# testx2.net
KiCad netlist of a schematic drawn in EAGLE
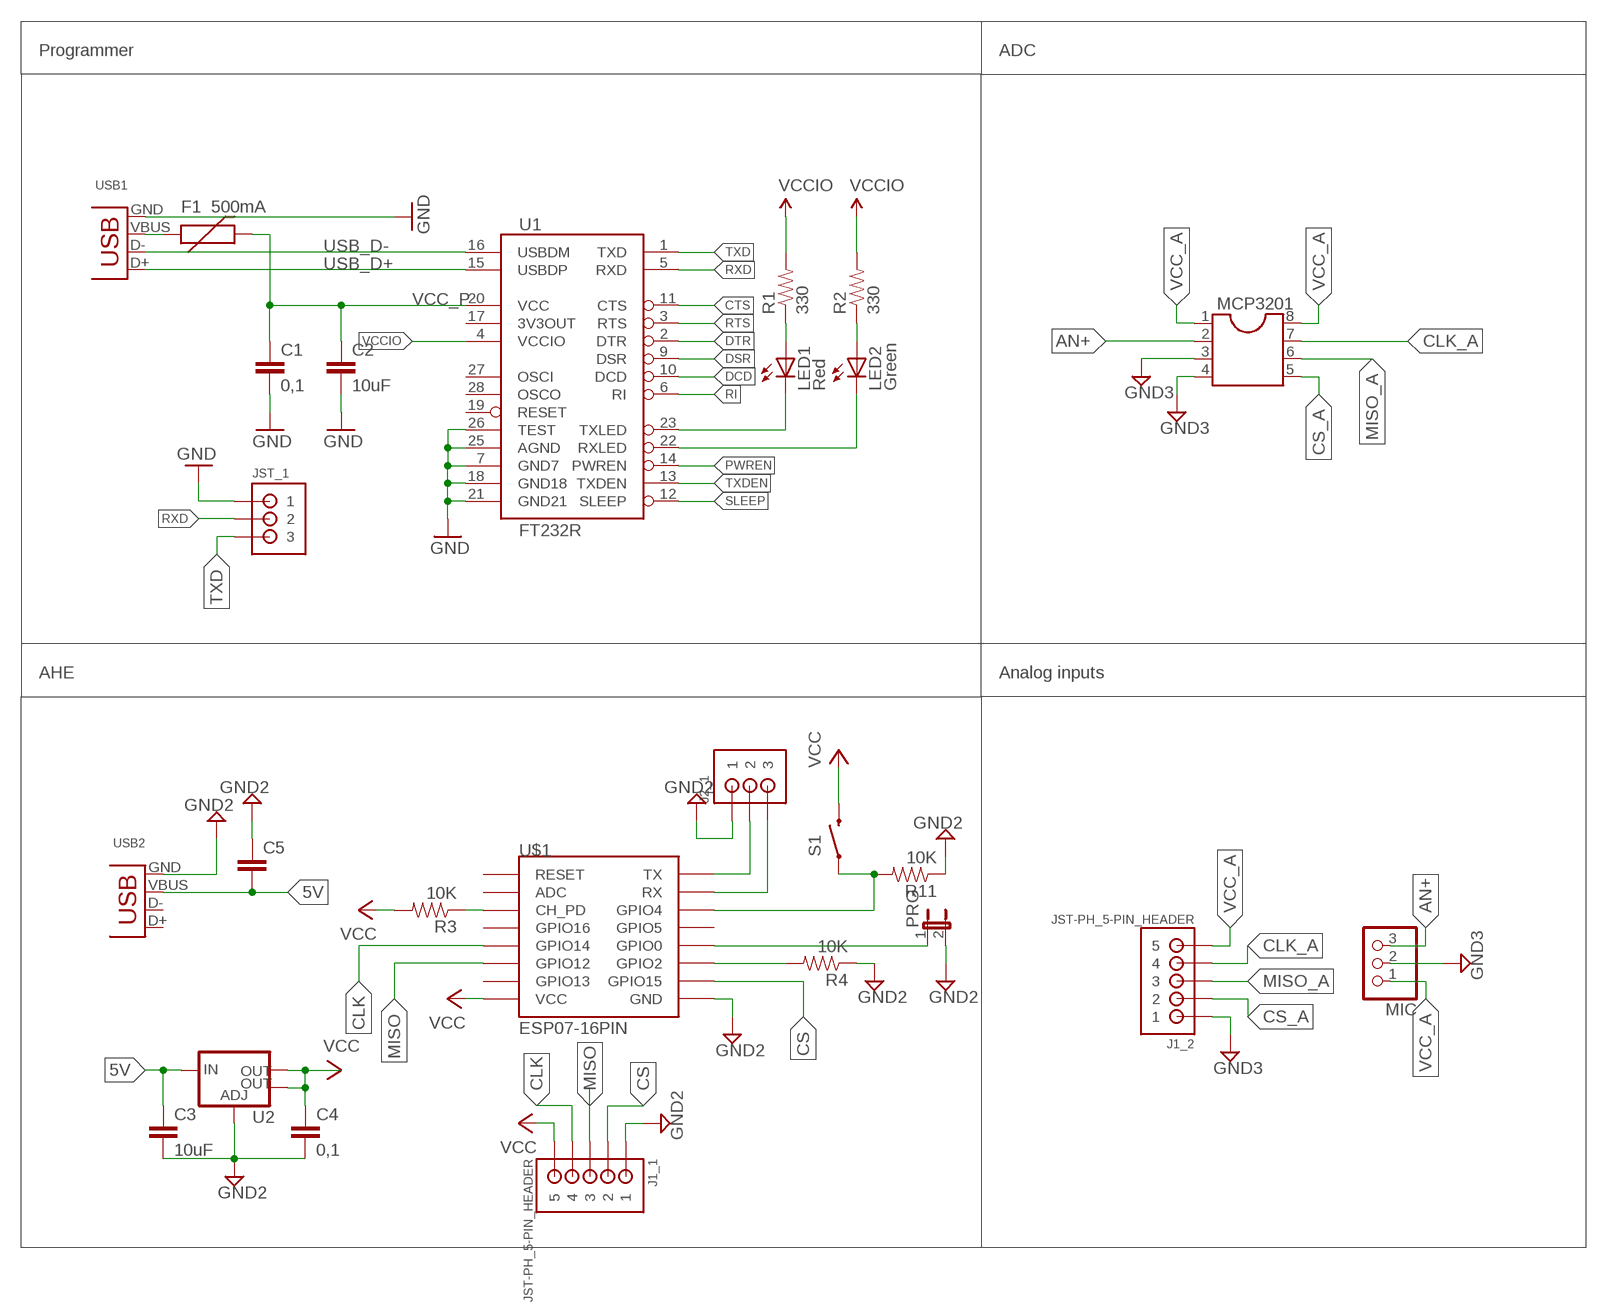
[diagram p0: schematic, sheet 1]
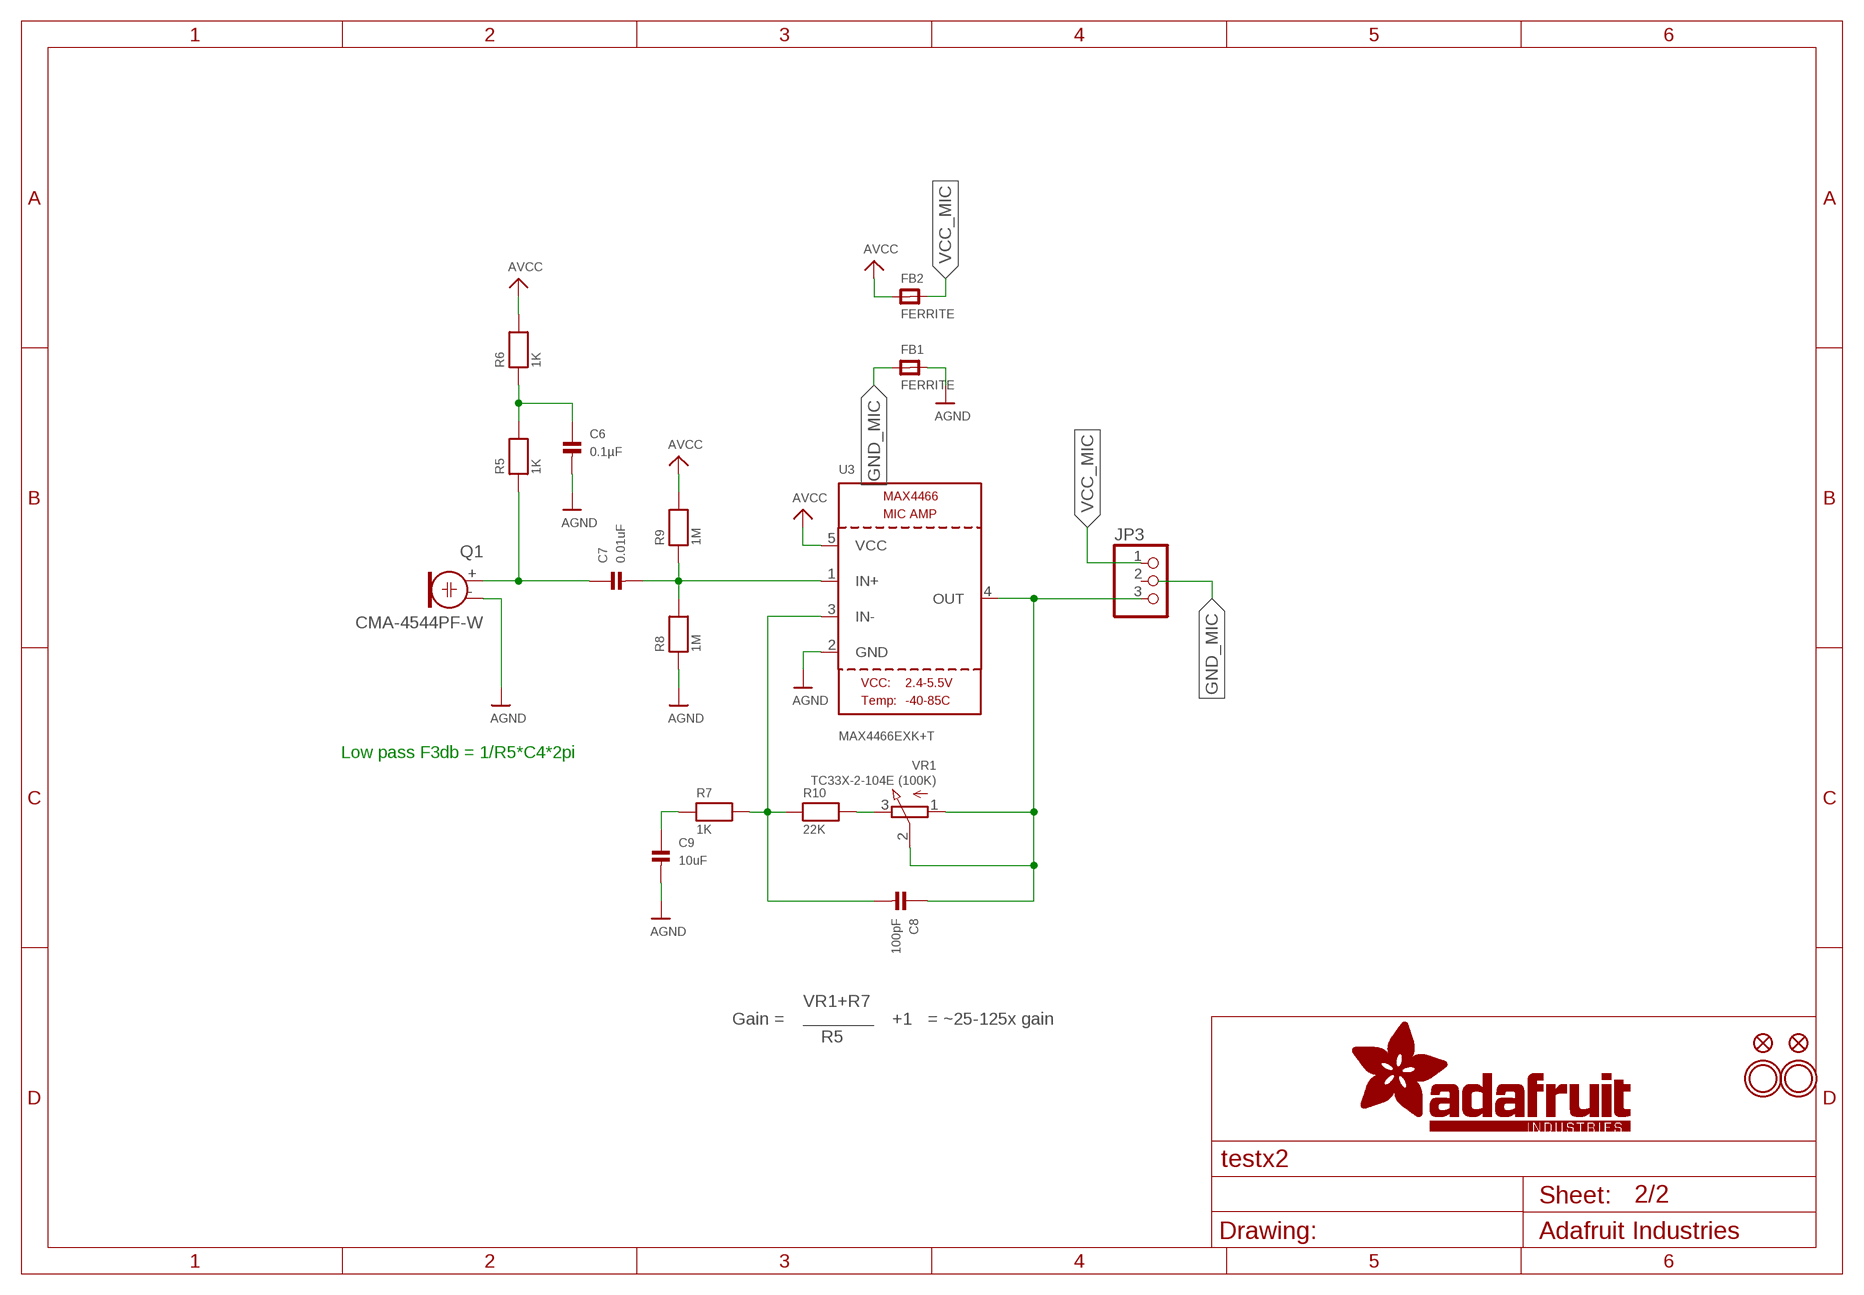
[diagram p1: schematic, sheet 2]

(export (version "E")
  (design (tool "Eeschema 10.0.6"))
  (components
    (comp (ref "C1")
      (value "0,1")
      (footprint "eagle-import:0805-CAP")
      (libsource (lib "eagle-import") (part "10UF10V10%(0805)"))
    )
    (comp (ref "C2")
      (value "10uF")
      (footprint "eagle-import:0805-CAP")
      (libsource (lib "eagle-import") (part "10UF10V10%(0805)"))
    )
    (comp (ref "C3")
      (value "10uF")
      (footprint "eagle-import:0805-CAP")
      (libsource (lib "eagle-import") (part "10UF10V10%(0805)"))
    )
    (comp (ref "C4")
      (value "0,1")
      (footprint "eagle-import:0805-CAP")
      (libsource (lib "eagle-import") (part "10UF10V10%(0805)"))
    )
    (comp (ref "C5")
      (value "CAP_")
      (footprint "eagle-import:AXIAL-5MM")
      (libsource (lib "eagle-import") (part "CAP_"))
    )
    (comp (ref "F1")
      (value "500mA")
      (footprint "eagle-import:PTC-1206")
      (libsource (lib "eagle-import") (part "PTCSMD"))
    )
    (comp (ref "J1_1")
      (value "JST-PH_5-PIN_HEADER")
      (footprint "eagle-import:JST_B5B-PH_HEADER")
      (libsource (lib "eagle-import") (part "JST-PH_5-PIN_HEADER"))
    )
    (comp (ref "J1_2")
      (value "JST-PH_5-PIN_HEADER")
      (footprint "eagle-import:JST_B5B-PH_HEADER")
      (libsource (lib "eagle-import") (part "JST-PH_5-PIN_HEADER"))
    )
    (comp (ref "J2_1")
      (value "JST-PH_3-PIN_HEADER")
      (footprint "eagle-import:JST_B3B-PH_HEADER")
      (libsource (lib "eagle-import") (part "JST-PH_3-PIN_HEADER"))
    )
    (comp (ref "JST_1")
      (value "JST-PH_3-PIN_HEADER")
      (footprint "eagle-import:JST_B3B-PH_HEADER")
      (libsource (lib "eagle-import") (part "JST-PH_3-PIN_HEADER"))
    )
    (comp (ref "LED1")
      (value "Red")
      (footprint "eagle-import:SML0805")
      (libsource (lib "eagle-import") (part "LEDSML0805"))
    )
    (comp (ref "LED2")
      (value "Green")
      (footprint "eagle-import:SML0805")
      (libsource (lib "eagle-import") (part "LEDSML0805"))
    )
    (comp (ref "MCP3201")
      (value "DIL8")
      (footprint "eagle-import:DIL08")
      (libsource (lib "eagle-import") (part "DIL8"))
    )
    (comp (ref "MIC")
      (value "PINHD-1X03_2.54-S")
      (footprint "eagle-import:1X03-S")
      (libsource (lib "eagle-import") (part "PINHD-1X03_2.54-S"))
    )
    (comp (ref "PRG")
      (value "JP1E")
      (footprint "eagle-import:JP1")
      (libsource (lib "eagle-import") (part "JP1E"))
    )
    (comp (ref "R1")
      (value "330")
      (footprint "eagle-import:0805")
      (libsource (lib "eagle-import") (part "0.22OHM-1/4W-1%(0805)"))
    )
    (comp (ref "R2")
      (value "330")
      (footprint "eagle-import:0805")
      (libsource (lib "eagle-import") (part "0.22OHM-1/4W-1%(0805)"))
    )
    (comp (ref "R3")
      (value "10K")
      (footprint "eagle-import:0805")
      (libsource (lib "eagle-import") (part "0.22OHM-1/4W-1%(0805)"))
    )
    (comp (ref "R4")
      (value "10K")
      (footprint "eagle-import:0805")
      (libsource (lib "eagle-import") (part "0.22OHM-1/4W-1%(0805)"))
    )
    (comp (ref "R11")
      (value "10K")
      (footprint "eagle-import:0805")
      (libsource (lib "eagle-import") (part "0.22OHM-1/4W-1%(0805)"))
    )
    (comp (ref "S1")
      (value "SWITCH-MOMENTARY-2PTH")
      (footprint "eagle-import:TACTILE-PTH")
      (libsource (lib "eagle-import") (part "SWITCH-MOMENTARY-2PTH"))
    )
    (comp (ref "U$1")
      (value "ESP07-16PIN")
      (footprint "eagle-import:ESP07-16PIN")
      (libsource (lib "eagle-import") (part "ESP07-16PIN"))
    )
    (comp (ref "U1")
      (value "FT232R")
      (footprint "eagle-import:SSOP28DB")
      (libsource (lib "eagle-import") (part "FT232RLSSOP"))
    )
    (comp (ref "U2")
      (value "V_REG_LM1117SOT223")
      (footprint "eagle-import:SOT223")
      (libsource (lib "eagle-import") (part "V_REG_LM1117SOT223"))
    )
    (comp (ref "USB1")
      (value "USB-MB-S")
      (footprint "eagle-import:USB-MB-S")
      (libsource (lib "eagle-import") (part "USB-MB-S"))
    )
    (comp (ref "USB2")
      (value "USB-MB-S")
      (footprint "eagle-import:USB-MB-S")
      (libsource (lib "eagle-import") (part "USB-MB-S"))
    )
    (comp (ref "C6")
      (value "0.1µF")
      (footprint "eagle-import:0805")
      (libsource (lib "eagle-import") (part "CAP_CERAMIC0805"))
    )
    (comp (ref "C7")
      (value "0.01uF")
      (footprint "eagle-import:0805")
      (libsource (lib "eagle-import") (part "CAP_CERAMIC0805"))
    )
    (comp (ref "C8")
      (value "100pF")
      (footprint "eagle-import:0805")
      (libsource (lib "eagle-import") (part "CAP_CERAMIC0805"))
    )
    (comp (ref "C9")
      (value "10uF")
      (footprint "eagle-import:0805")
      (libsource (lib "eagle-import") (part "CAP_CERAMIC0805"))
    )
    (comp (ref "FB1")
      (value "FERRITE")
      (footprint "eagle-import:0805")
      (libsource (lib "eagle-import") (part "FERRITE0805"))
    )
    (comp (ref "FB2")
      (value "FERRITE")
      (footprint "eagle-import:0805")
      (libsource (lib "eagle-import") (part "FERRITE0805"))
    )
    (comp (ref "FID1")
      (value "FIDUCIAL\"\"")
      (footprint "eagle-import:FIDUCIAL_1MM")
      (libsource (lib "eagle-import") (part "FIDUCIAL{dblquote}{dblquote}"))
    )
    (comp (ref "FID2")
      (value "FIDUCIAL\"\"")
      (footprint "eagle-import:FIDUCIAL_1MM")
      (libsource (lib "eagle-import") (part "FIDUCIAL{dblquote}{dblquote}"))
    )
    (comp (ref "JP3")
      (value "HEADER-1X376MIL")
      (footprint "eagle-import:1X03_ROUND_76")
      (libsource (lib "eagle-import") (part "HEADER-1X376MIL"))
    )
    (comp (ref "Q1")
      (value "CMA-4544PF-W")
      (footprint "eagle-import:ELECTRET_9.7")
      (libsource (lib "eagle-import") (part "ELECTRET"))
    )
    (comp (ref "R5")
      (value "1K")
      (footprint "eagle-import:0805")
      (libsource (lib "eagle-import") (part "RESISTOR0805"))
    )
    (comp (ref "R6")
      (value "1K")
      (footprint "eagle-import:0805")
      (libsource (lib "eagle-import") (part "RESISTOR0805"))
    )
    (comp (ref "R7")
      (value "1K")
      (footprint "eagle-import:0805")
      (libsource (lib "eagle-import") (part "RESISTOR0805"))
    )
    (comp (ref "R8")
      (value "1M")
      (footprint "eagle-import:0805")
      (libsource (lib "eagle-import") (part "RESISTOR0805"))
    )
    (comp (ref "R9")
      (value "1M")
      (footprint "eagle-import:0805")
      (libsource (lib "eagle-import") (part "RESISTOR0805"))
    )
    (comp (ref "R10")
      (value "22K")
      (footprint "eagle-import:0805")
      (libsource (lib "eagle-import") (part "RESISTOR0805"))
    )
    (comp (ref "U$16")
      (value "MOUNTINGHOLE2.5")
      (footprint "eagle-import:MOUNTINGHOLE_2.5_PLATED")
      (libsource (lib "eagle-import") (part "MOUNTINGHOLE2.5"))
    )
    (comp (ref "U$17")
      (value "MOUNTINGHOLE2.5")
      (footprint "eagle-import:MOUNTINGHOLE_2.5_PLATED")
      (libsource (lib "eagle-import") (part "MOUNTINGHOLE2.5"))
    )
    (comp (ref "U3")
      (value "MAX4466EXK+T")
      (footprint "eagle-import:SC70-5")
      (libsource (lib "eagle-import") (part "MAX4466{dblquote}{dblquote}"))
    )
    (comp (ref "VR1")
      (value "TC33X-2-104E (100K)")
      (footprint "eagle-import:TRIMPOT_BOURNS_TC33X-2")
      (libsource (lib "eagle-import") (part "TRIMPOTTC33X-2"))
    )
  )
  (nets
    (net (code "1") (name "5V") (class "Default")
      (node (ref "C3") (pin "1") (pinfunction "1_1") (pintype "passive"))
      (node (ref "C5") (pin "P$2") (pinfunction "2_P$2") (pintype "passive"))
      (node (ref "U2") (pin "3") (pinfunction "IN_3") (pintype "input"))
      (node (ref "USB2") (pin "VBUS") (pinfunction "VBUS_VBUS") (pintype "bidirectional"))
    )
    (net (code "2") (name "AGND") (class "Default")
      (node (ref "C6") (pin "2") (pinfunction "P$2_2") (pintype "passive"))
      (node (ref "C9") (pin "2") (pinfunction "P$2_2") (pintype "passive"))
      (node (ref "FB1") (pin "2") (pinfunction "P$2_2") (pintype "passive"))
      (node (ref "Q1") (pin "-") (pinfunction "1_-") (pintype "passive"))
      (node (ref "R8") (pin "1") (pinfunction "1_1") (pintype "passive"))
      (node (ref "U3") (pin "2") (pinfunction "GND_2") (pintype "bidirectional"))
    )
    (net (code "3") (name "AN+") (class "Default")
      (node (ref "MCP3201") (pin "2") (pinfunction "2_2") (pintype "passive"))
      (node (ref "MIC") (pin "3") (pinfunction "3_3") (pintype "passive"))
    )
    (net (code "4") (name "AVCC") (class "Default")
      (node (ref "FB2") (pin "1") (pinfunction "P$1_1") (pintype "passive"))
      (node (ref "R6") (pin "2") (pinfunction "2_2") (pintype "passive"))
      (node (ref "R9") (pin "2") (pinfunction "2_2") (pintype "passive"))
      (node (ref "U3") (pin "5") (pinfunction "VCC_5") (pintype "bidirectional"))
    )
    (net (code "5") (name "CLK") (class "Default")
      (node (ref "J1_1") (pin "P4") (pinfunction "4_P4") (pintype "bidirectional"))
      (node (ref "U$1") (pin "GPIO14") (pinfunction "GPIO14_GPIO14") (pintype "bidirectional"))
    )
    (net (code "6") (name "CLK_A") (class "Default")
      (node (ref "J1_2") (pin "P4") (pinfunction "4_P4") (pintype "bidirectional"))
      (node (ref "MCP3201") (pin "7") (pinfunction "7_7") (pintype "passive"))
    )
    (net (code "7") (name "CS") (class "Default")
      (node (ref "J1_1") (pin "P2") (pinfunction "2_P2") (pintype "bidirectional"))
      (node (ref "U$1") (pin "GPIO15") (pinfunction "GPIO15_GPIO15") (pintype "bidirectional"))
    )
    (net (code "8") (name "CS_A") (class "Default")
      (node (ref "J1_2") (pin "P2") (pinfunction "2_P2") (pintype "bidirectional"))
      (node (ref "MCP3201") (pin "5") (pinfunction "5_5") (pintype "passive"))
    )
    (net (code "9") (name "CTS") (class "Default")
      (node (ref "U1") (pin "11") (pinfunction "CTS_11") (pintype "input"))
    )
    (net (code "10") (name "DCD") (class "Default")
      (node (ref "U1") (pin "10") (pinfunction "DCD_10") (pintype "input"))
    )
    (net (code "11") (name "DSR") (class "Default")
      (node (ref "U1") (pin "9") (pinfunction "DSR_9") (pintype "input"))
    )
    (net (code "12") (name "DTR") (class "Default")
      (node (ref "U1") (pin "2") (pinfunction "DTR_2") (pintype "output"))
    )
    (net (code "13") (name "GND") (class "Default")
      (node (ref "C1") (pin "2") (pinfunction "2_2") (pintype "passive"))
      (node (ref "C2") (pin "2") (pinfunction "2_2") (pintype "passive"))
      (node (ref "JST_1") (pin "P1") (pinfunction "1_P1") (pintype "bidirectional"))
      (node (ref "U1") (pin "18") (pinfunction "GND18_18") (pintype "power_in"))
      (node (ref "U1") (pin "21") (pinfunction "GND21_21") (pintype "power_in"))
      (node (ref "U1") (pin "25") (pinfunction "AGND_25") (pintype "power_in"))
      (node (ref "U1") (pin "26") (pinfunction "TEST_26") (pintype "input"))
      (node (ref "U1") (pin "7") (pinfunction "GND7_7") (pintype "power_in"))
      (node (ref "USB1") (pin "GND") (pinfunction "GND_GND") (pintype "bidirectional"))
    )
    (net (code "14") (name "GND2") (class "Default")
      (node (ref "C3") (pin "2") (pinfunction "2_2") (pintype "passive"))
      (node (ref "C4") (pin "2") (pinfunction "2_2") (pintype "passive"))
      (node (ref "C5") (pin "P$1") (pinfunction "1_P$1") (pintype "passive"))
      (node (ref "J1_1") (pin "P1") (pinfunction "1_P1") (pintype "bidirectional"))
      (node (ref "J2_1") (pin "P1") (pinfunction "1_P1") (pintype "bidirectional"))
      (node (ref "PRG") (pin "2") (pinfunction "2_2") (pintype "passive"))
      (node (ref "R11") (pin "1") (pinfunction "1_1") (pintype "passive"))
      (node (ref "R4") (pin "1") (pinfunction "1_1") (pintype "passive"))
      (node (ref "U$1") (pin "GND") (pinfunction "GND_GND") (pintype "bidirectional"))
      (node (ref "U2") (pin "1") (pinfunction "ADJ_1") (pintype "input"))
      (node (ref "USB2") (pin "GND") (pinfunction "GND_GND") (pintype "bidirectional"))
    )
    (net (code "15") (name "GND3") (class "Default")
      (node (ref "J1_2") (pin "P1") (pinfunction "1_P1") (pintype "bidirectional"))
      (node (ref "MCP3201") (pin "3") (pinfunction "3_3") (pintype "passive"))
      (node (ref "MCP3201") (pin "4") (pinfunction "4_4") (pintype "passive"))
      (node (ref "MIC") (pin "2") (pinfunction "2_2") (pintype "passive"))
    )
    (net (code "16") (name "GND_MIC") (class "Default")
      (node (ref "FB1") (pin "1") (pinfunction "P$1_1") (pintype "passive"))
    )
    (net (code "17") (name "MISO") (class "Default")
      (node (ref "J1_1") (pin "P3") (pinfunction "3_P3") (pintype "bidirectional"))
      (node (ref "U$1") (pin "GPIO12") (pinfunction "GPIO12_GPIO12") (pintype "bidirectional"))
    )
    (net (code "18") (name "MISO_A") (class "Default")
      (node (ref "J1_2") (pin "P3") (pinfunction "3_P3") (pintype "bidirectional"))
      (node (ref "MCP3201") (pin "6") (pinfunction "6_6") (pintype "passive"))
    )
    (net (code "19") (name "Net-(C6-P$1)") (class "Default")
      (node (ref "C6") (pin "1") (pinfunction "P$1_1") (pintype "passive"))
      (node (ref "R5") (pin "2") (pinfunction "2_2") (pintype "passive"))
      (node (ref "R6") (pin "1") (pinfunction "1_1") (pintype "passive"))
    )
    (net (code "20") (name "Net-(C7-P$1)") (class "Default")
      (node (ref "C7") (pin "1") (pinfunction "P$1_1") (pintype "passive"))
      (node (ref "Q1") (pin "+") (pinfunction "2_+") (pintype "passive"))
      (node (ref "R5") (pin "1") (pinfunction "1_1") (pintype "passive"))
    )
    (net (code "21") (name "Net-(C7-P$2)") (class "Default")
      (node (ref "C7") (pin "2") (pinfunction "P$2_2") (pintype "passive"))
      (node (ref "R8") (pin "2") (pinfunction "2_2") (pintype "passive"))
      (node (ref "R9") (pin "1") (pinfunction "1_1") (pintype "passive"))
      (node (ref "U3") (pin "1") (pinfunction "IN+_1") (pintype "bidirectional"))
    )
    (net (code "22") (name "Net-(C8-P$1)") (class "Default")
      (node (ref "C8") (pin "1") (pinfunction "P$1_1") (pintype "passive"))
      (node (ref "JP3") (pin "3") (pinfunction "3_3") (pintype "passive"))
      (node (ref "U3") (pin "4") (pinfunction "OUT_4") (pintype "bidirectional"))
      (node (ref "VR1") (pin "1") (pinfunction "A_1") (pintype "passive"))
      (node (ref "VR1") (pin "2") (pinfunction "S_2") (pintype "passive"))
    )
    (net (code "23") (name "Net-(C8-P$2)") (class "Default")
      (node (ref "C8") (pin "2") (pinfunction "P$2_2") (pintype "passive"))
      (node (ref "R10") (pin "1") (pinfunction "1_1") (pintype "passive"))
      (node (ref "R7") (pin "2") (pinfunction "2_2") (pintype "passive"))
      (node (ref "U3") (pin "3") (pinfunction "IN-_3") (pintype "bidirectional"))
    )
    (net (code "24") (name "Net-(C9-P$1)") (class "Default")
      (node (ref "C9") (pin "1") (pinfunction "P$1_1") (pintype "passive"))
      (node (ref "R7") (pin "1") (pinfunction "1_1") (pintype "passive"))
    )
    (net (code "25") (name "Net-(F1-Pad1)") (class "Default")
      (node (ref "F1") (pin "1") (pinfunction "1_1") (pintype "bidirectional"))
      (node (ref "USB1") (pin "VBUS") (pinfunction "VBUS_VBUS") (pintype "bidirectional"))
    )
    (net (code "26") (name "Net-(J2_1-2)") (class "Default")
      (node (ref "J2_1") (pin "P2") (pinfunction "2_P2") (pintype "bidirectional"))
      (node (ref "U$1") (pin "TX") (pinfunction "TX_TX") (pintype "bidirectional"))
    )
    (net (code "27") (name "Net-(J2_1-3)") (class "Default")
      (node (ref "J2_1") (pin "P3") (pinfunction "3_P3") (pintype "bidirectional"))
      (node (ref "U$1") (pin "RX") (pinfunction "RX_RX") (pintype "bidirectional"))
    )
    (net (code "28") (name "Net-(LED1-PadA)") (class "Default")
      (node (ref "LED1") (pin "A") (pinfunction "A_A") (pintype "passive"))
      (node (ref "R1") (pin "1") (pinfunction "1_1") (pintype "passive"))
    )
    (net (code "29") (name "Net-(LED2-PadA)") (class "Default")
      (node (ref "LED2") (pin "A") (pinfunction "A_A") (pintype "passive"))
      (node (ref "R2") (pin "1") (pinfunction "1_1") (pintype "passive"))
    )
    (net (code "30") (name "Net-(PRG-Pad1)") (class "Default")
      (node (ref "PRG") (pin "1") (pinfunction "1_1") (pintype "passive"))
      (node (ref "U$1") (pin "GPIO0") (pinfunction "GPIO0_GPIO0") (pintype "bidirectional"))
    )
    (net (code "31") (name "Net-(R3-Pad1)") (class "Default")
      (node (ref "R3") (pin "1") (pinfunction "1_1") (pintype "passive"))
      (node (ref "U$1") (pin "CH_PD") (pinfunction "CH_PD_CH_PD") (pintype "bidirectional"))
    )
    (net (code "32") (name "Net-(R4-Pad2)") (class "Default")
      (node (ref "R4") (pin "2") (pinfunction "2_2") (pintype "passive"))
      (node (ref "U$1") (pin "GPIO2") (pinfunction "GPIO2_GPIO2") (pintype "bidirectional"))
    )
    (net (code "33") (name "Net-(R11-Pad2)") (class "Default")
      (node (ref "R11") (pin "2") (pinfunction "2_2") (pintype "passive"))
      (node (ref "S1") (pin "1") (pinfunction "1_1") (pintype "passive"))
      (node (ref "U$1") (pin "GPIO4") (pinfunction "GPIO4_GPIO4") (pintype "bidirectional"))
    )
    (net (code "34") (name "Net-(U1-RXLED)") (class "Default")
      (node (ref "LED2") (pin "C") (pinfunction "C_C") (pintype "passive"))
      (node (ref "U1") (pin "22") (pinfunction "RXLED_22") (pintype "input"))
    )
    (net (code "35") (name "Net-(U1-TXLED)") (class "Default")
      (node (ref "LED1") (pin "C") (pinfunction "C_C") (pintype "passive"))
      (node (ref "U1") (pin "23") (pinfunction "TXLED_23") (pintype "input"))
    )
    (net (code "36") (name "Net-(VR1-E)") (class "Default")
      (node (ref "R10") (pin "2") (pinfunction "2_2") (pintype "passive"))
      (node (ref "VR1") (pin "3") (pinfunction "E_3") (pintype "passive"))
    )
    (net (code "37") (name "PWREN") (class "Default")
      (node (ref "U1") (pin "14") (pinfunction "PWREN_14") (pintype "input"))
    )
    (net (code "38") (name "RI") (class "Default")
      (node (ref "U1") (pin "6") (pinfunction "RI_6") (pintype "input"))
    )
    (net (code "39") (name "RTS") (class "Default")
      (node (ref "U1") (pin "3") (pinfunction "RTS_3") (pintype "output"))
    )
    (net (code "40") (name "RXD") (class "Default")
      (node (ref "JST_1") (pin "P2") (pinfunction "2_P2") (pintype "bidirectional"))
      (node (ref "U1") (pin "5") (pinfunction "RXD_5") (pintype "input"))
    )
    (net (code "41") (name "SLEEP") (class "Default")
      (node (ref "U1") (pin "12") (pinfunction "SLEEP_12") (pintype "input"))
    )
    (net (code "42") (name "TXD") (class "Default")
      (node (ref "JST_1") (pin "P3") (pinfunction "3_P3") (pintype "bidirectional"))
      (node (ref "U1") (pin "1") (pinfunction "TXD_1") (pintype "output"))
    )
    (net (code "43") (name "TXDEN") (class "Default")
      (node (ref "U1") (pin "13") (pinfunction "TXDEN_13") (pintype "input"))
    )
    (net (code "44") (name "USB_D+") (class "Default")
      (node (ref "U1") (pin "15") (pinfunction "USBDP_15") (pintype "bidirectional"))
      (node (ref "USB1") (pin "D+") (pinfunction "D+_D+") (pintype "bidirectional"))
    )
    (net (code "45") (name "USB_D-") (class "Default")
      (node (ref "U1") (pin "16") (pinfunction "USBDM_16") (pintype "bidirectional"))
      (node (ref "USB1") (pin "D-") (pinfunction "D-_D-") (pintype "bidirectional"))
    )
    (net (code "46") (name "VCC") (class "Default")
      (node (ref "C4") (pin "1") (pinfunction "1_1") (pintype "passive"))
      (node (ref "J1_1") (pin "P5") (pinfunction "5_P5") (pintype "bidirectional"))
      (node (ref "R3") (pin "2") (pinfunction "2_2") (pintype "passive"))
      (node (ref "S1") (pin "3") (pinfunction "2_3") (pintype "passive"))
      (node (ref "U$1") (pin "VCC") (pinfunction "VCC_VCC") (pintype "bidirectional"))
      (node (ref "U2") (pin "2") (pinfunction "OUT_2") (pintype "output"))
      (node (ref "U2") (pin "4") (pinfunction "OUT_4") (pintype "output"))
    )
    (net (code "47") (name "VCCIO") (class "Default")
      (node (ref "R1") (pin "2") (pinfunction "2_2") (pintype "passive"))
      (node (ref "R2") (pin "2") (pinfunction "2_2") (pintype "passive"))
      (node (ref "U1") (pin "4") (pinfunction "VCCIO_4") (pintype "power_in"))
    )
    (net (code "48") (name "VCC_A") (class "Default")
      (node (ref "J1_2") (pin "P5") (pinfunction "5_P5") (pintype "bidirectional"))
      (node (ref "MCP3201") (pin "1") (pinfunction "1_1") (pintype "passive"))
      (node (ref "MCP3201") (pin "8") (pinfunction "8_8") (pintype "passive"))
      (node (ref "MIC") (pin "1") (pinfunction "1_1") (pintype "passive"))
    )
    (net (code "49") (name "VCC_MIC") (class "Default")
      (node (ref "FB2") (pin "2") (pinfunction "P$2_2") (pintype "passive"))
      (node (ref "JP3") (pin "1") (pinfunction "1_1") (pintype "passive"))
    )
    (net (code "50") (name "VCC_P") (class "Default")
      (node (ref "C1") (pin "1") (pinfunction "1_1") (pintype "passive"))
      (node (ref "C2") (pin "1") (pinfunction "1_1") (pintype "passive"))
      (node (ref "F1") (pin "2") (pinfunction "2_2") (pintype "bidirectional"))
      (node (ref "U1") (pin "20") (pinfunction "VCC_20") (pintype "power_in"))
    )
    (net (code "51") (name "unconnected-(JP3-Pad2)") (class "Default")
      (node (ref "JP3") (pin "2") (pinfunction "2_2") (pintype "passive"))
    )
    (net (code "52") (name "unconnected-(U$1-PadADC)") (class "Default")
      (node (ref "U$1") (pin "ADC") (pinfunction "ADC_ADC") (pintype "bidirectional"))
    )
    (net (code "53") (name "unconnected-(U$1-PadGPIO5)") (class "Default")
      (node (ref "U$1") (pin "GPIO5") (pinfunction "GPIO5_GPIO5") (pintype "bidirectional"))
    )
    (net (code "54") (name "unconnected-(U$1-PadGPIO13)") (class "Default")
      (node (ref "U$1") (pin "GPIO13") (pinfunction "GPIO13_GPIO13") (pintype "bidirectional"))
    )
    (net (code "55") (name "unconnected-(U$1-PadGPIO16)") (class "Default")
      (node (ref "U$1") (pin "GPIO16") (pinfunction "GPIO16_GPIO16") (pintype "bidirectional"))
    )
    (net (code "56") (name "unconnected-(U$1-RESET-PadREST)") (class "Default")
      (node (ref "U$1") (pin "REST") (pinfunction "RESET_REST") (pintype "bidirectional"))
    )
    (net (code "57") (name "unconnected-(U1-3V3OUT-Pad17)") (class "Default")
      (node (ref "U1") (pin "17") (pinfunction "3V3OUT_17") (pintype "output"))
    )
    (net (code "58") (name "unconnected-(U1-OSCI-Pad27)") (class "Default")
      (node (ref "U1") (pin "27") (pinfunction "OSCI_27") (pintype "input"))
    )
    (net (code "59") (name "unconnected-(U1-OSCO-Pad28)") (class "Default")
      (node (ref "U1") (pin "28") (pinfunction "OSCO_28") (pintype "output"))
    )
    (net (code "60") (name "unconnected-(U1-RESET-Pad19)") (class "Default")
      (node (ref "U1") (pin "19") (pinfunction "RESET_19") (pintype "input"))
    )
    (net (code "61") (name "unconnected-(USB2-PadD+)") (class "Default")
      (node (ref "USB2") (pin "D+") (pinfunction "D+_D+") (pintype "bidirectional"))
    )
    (net (code "62") (name "unconnected-(USB2-PadD-)") (class "Default")
      (node (ref "USB2") (pin "D-") (pinfunction "D-_D-") (pintype "bidirectional"))
    )
  )
)
